# TOP.net
KiCad netlist of a schematic drawn in Altium Designer
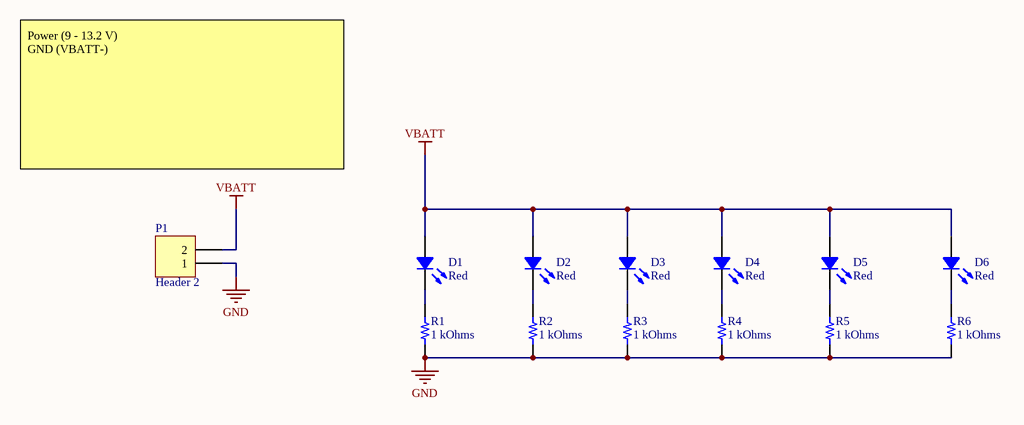
[diagram p0: TOP.SchDoc]

(export (version "E")
  (design (tool "Eeschema 10.0.6"))
  (components
    (comp (ref "D1")
      (value "Red")
      (footprint "LED 1206_3216 RED")
      (description "LED SMD")
      (fields (field (name "PART NUMBER") "APTR3216SECK/J3-PRV") (field (name "MANUFACTURER") "Kingbright"))
      (libsource (lib "Celestial") (part "LED"))
    )
    (comp (ref "D2")
      (value "Red")
      (footprint "LED 1206_3216 RED")
      (description "LED SMD")
      (fields (field (name "PART NUMBER") "APTR3216SECK/J3-PRV") (field (name "MANUFACTURER") "Kingbright"))
      (libsource (lib "Celestial") (part "LED"))
    )
    (comp (ref "D3")
      (value "Red")
      (footprint "LED 1206_3216 RED")
      (description "LED SMD")
      (fields (field (name "PART NUMBER") "APTR3216SECK/J3-PRV") (field (name "MANUFACTURER") "Kingbright"))
      (libsource (lib "Celestial") (part "LED"))
    )
    (comp (ref "D4")
      (value "Red")
      (footprint "LED 1206_3216 RED")
      (description "LED SMD")
      (fields (field (name "PART NUMBER") "APTR3216SECK/J3-PRV") (field (name "MANUFACTURER") "Kingbright"))
      (libsource (lib "Celestial") (part "LED"))
    )
    (comp (ref "D5")
      (value "Red")
      (footprint "LED 1206_3216 RED")
      (description "LED SMD")
      (fields (field (name "PART NUMBER") "APTR3216SECK/J3-PRV") (field (name "MANUFACTURER") "Kingbright"))
      (libsource (lib "Celestial") (part "LED"))
    )
    (comp (ref "D6")
      (value "Red")
      (footprint "LED 1206_3216 RED")
      (description "LED SMD")
      (fields (field (name "PART NUMBER") "APTR3216SECK/J3-PRV") (field (name "MANUFACTURER") "Kingbright"))
      (libsource (lib "Celestial") (part "LED"))
    )
    (comp (ref "P1")
      (value "Header 2")
      (footprint "HDR1X2")
      (description "Header, 2-Pin")
      (fields (field (name "PUBLISHER") "Altium Limited"))
      (libsource (lib "Miscellaneous Connectors") (part "Header 2"))
    )
    (comp (ref "R1")
      (value "1 kOhms")
      (footprint "RES 0402_1005")
      (description "RES SMD 1K OHM 0.1% 1/16W 0402")
      (fields (field (name "PART NUMBER") "AT0402BRD071KL") (field (name "MANUFACTURER") "Yageo"))
      (libsource (lib "Celestial") (part "Resistor"))
    )
    (comp (ref "R2")
      (value "1 kOhms")
      (footprint "RES 0402_1005")
      (description "RES SMD 1K OHM 0.1% 1/16W 0402")
      (fields (field (name "PART NUMBER") "AT0402BRD071KL") (field (name "MANUFACTURER") "Yageo"))
      (libsource (lib "Celestial") (part "Resistor"))
    )
    (comp (ref "R3")
      (value "1 kOhms")
      (footprint "RES 0402_1005")
      (description "RES SMD 1K OHM 0.1% 1/16W 0402")
      (fields (field (name "PART NUMBER") "AT0402BRD071KL") (field (name "MANUFACTURER") "Yageo"))
      (libsource (lib "Celestial") (part "Resistor"))
    )
    (comp (ref "R4")
      (value "1 kOhms")
      (footprint "RES 0402_1005")
      (description "RES SMD 1K OHM 0.1% 1/16W 0402")
      (fields (field (name "PART NUMBER") "AT0402BRD071KL") (field (name "MANUFACTURER") "Yageo"))
      (libsource (lib "Celestial") (part "Resistor"))
    )
    (comp (ref "R5")
      (value "1 kOhms")
      (footprint "RES 0402_1005")
      (description "RES SMD 1K OHM 0.1% 1/16W 0402")
      (fields (field (name "PART NUMBER") "AT0402BRD071KL") (field (name "MANUFACTURER") "Yageo"))
      (libsource (lib "Celestial") (part "Resistor"))
    )
    (comp (ref "R6")
      (value "1 kOhms")
      (footprint "RES 0402_1005")
      (description "RES SMD 1K OHM 0.1% 1/16W 0402")
      (fields (field (name "PART NUMBER") "AT0402BRD071KL") (field (name "MANUFACTURER") "Yageo"))
      (libsource (lib "Celestial") (part "Resistor"))
    )
  )
  (nets
    (net (code "1") (name "GND") (class "Default")
      (node (ref "P1") (pin "1") (pinfunction "1_1") (pintype "passive"))
      (node (ref "R1") (pin "1") (pinfunction "1_1") (pintype "passive"))
      (node (ref "R2") (pin "1") (pinfunction "1_1") (pintype "passive"))
      (node (ref "R3") (pin "1") (pinfunction "1_1") (pintype "passive"))
      (node (ref "R4") (pin "1") (pinfunction "1_1") (pintype "passive"))
      (node (ref "R5") (pin "1") (pinfunction "1_1") (pintype "passive"))
      (node (ref "R6") (pin "1") (pinfunction "1_1") (pintype "passive"))
    )
    (net (code "2") (name "Net-(D1-Pad2)") (class "Default")
      (node (ref "D1") (pin "2") (pinfunction "2_2") (pintype "passive"))
      (node (ref "R1") (pin "2") (pinfunction "2_2") (pintype "passive"))
    )
    (net (code "3") (name "Net-(D2-Pad2)") (class "Default")
      (node (ref "D2") (pin "2") (pinfunction "2_2") (pintype "passive"))
      (node (ref "R2") (pin "2") (pinfunction "2_2") (pintype "passive"))
    )
    (net (code "4") (name "Net-(D3-Pad2)") (class "Default")
      (node (ref "D3") (pin "2") (pinfunction "2_2") (pintype "passive"))
      (node (ref "R3") (pin "2") (pinfunction "2_2") (pintype "passive"))
    )
    (net (code "5") (name "Net-(D4-Pad2)") (class "Default")
      (node (ref "D4") (pin "2") (pinfunction "2_2") (pintype "passive"))
      (node (ref "R4") (pin "2") (pinfunction "2_2") (pintype "passive"))
    )
    (net (code "6") (name "Net-(D5-Pad2)") (class "Default")
      (node (ref "D5") (pin "2") (pinfunction "2_2") (pintype "passive"))
      (node (ref "R5") (pin "2") (pinfunction "2_2") (pintype "passive"))
    )
    (net (code "7") (name "Net-(D6-Pad2)") (class "Default")
      (node (ref "D6") (pin "2") (pinfunction "2_2") (pintype "passive"))
      (node (ref "R6") (pin "2") (pinfunction "2_2") (pintype "passive"))
    )
    (net (code "8") (name "VBATT") (class "Default")
      (node (ref "D1") (pin "1") (pinfunction "1_1") (pintype "passive"))
      (node (ref "D2") (pin "1") (pinfunction "1_1") (pintype "passive"))
      (node (ref "D3") (pin "1") (pinfunction "1_1") (pintype "passive"))
      (node (ref "D4") (pin "1") (pinfunction "1_1") (pintype "passive"))
      (node (ref "D5") (pin "1") (pinfunction "1_1") (pintype "passive"))
      (node (ref "D6") (pin "1") (pinfunction "1_1") (pintype "passive"))
      (node (ref "P1") (pin "2") (pinfunction "2_2") (pintype "passive"))
    )
  )
)
